# Sheet1.net
KiCad netlist of a schematic drawn in Altium Designer
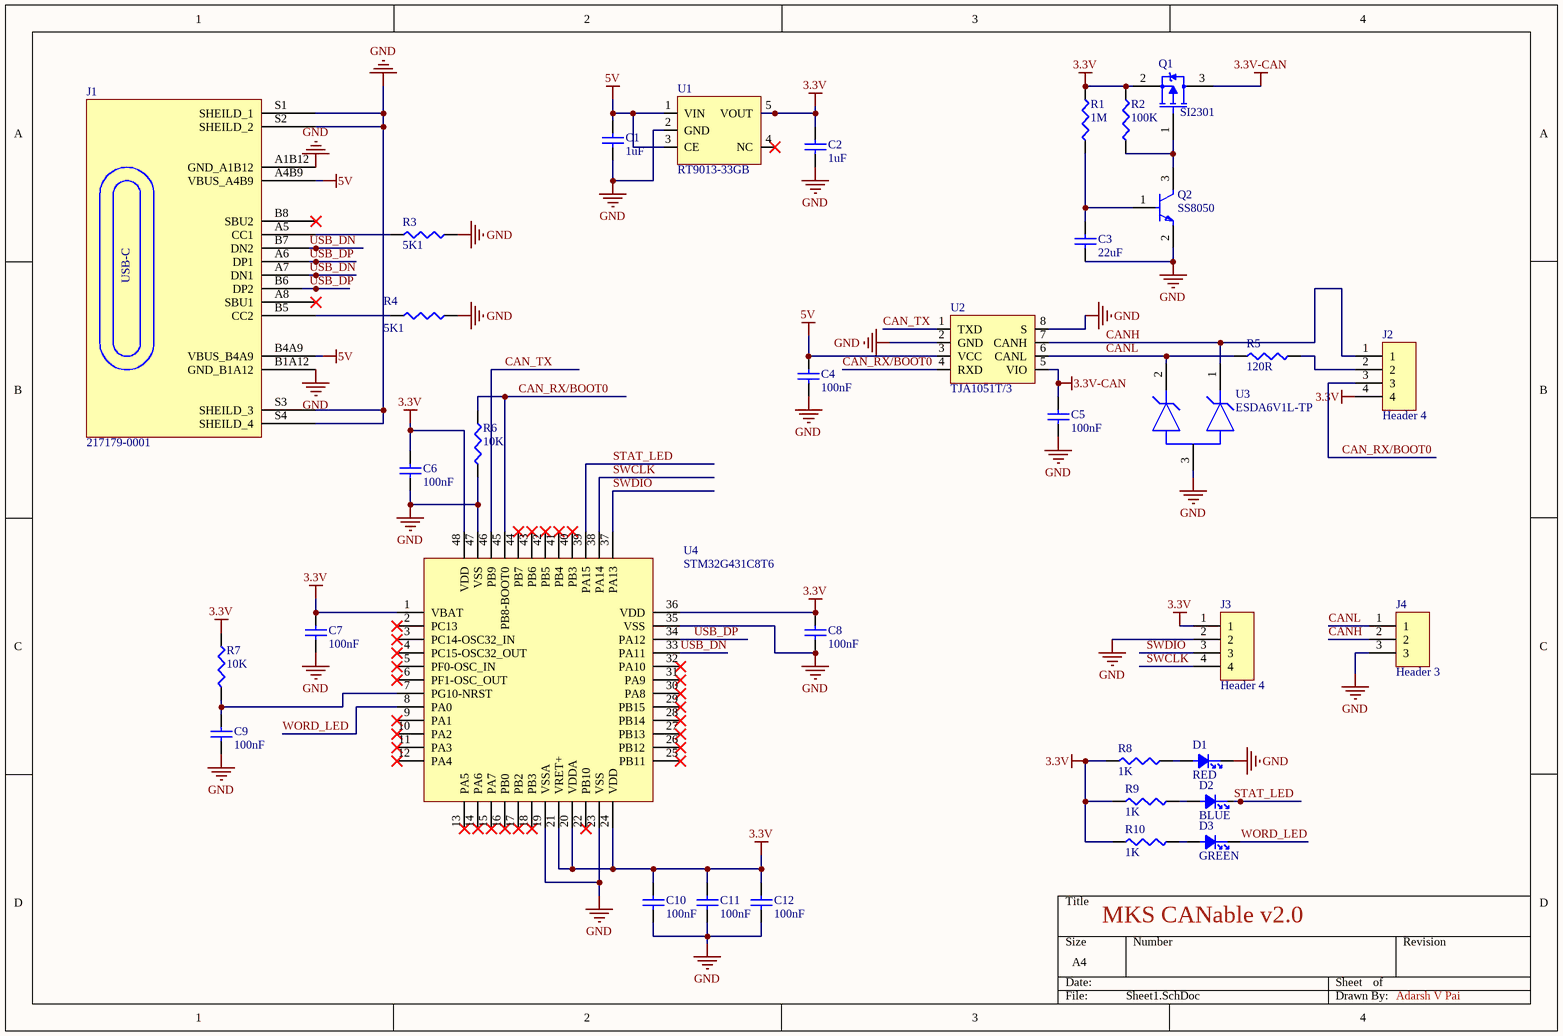
[diagram p0: Sheet1.SchDoc]

(export (version "E")
  (design (tool "Eeschema 10.0.6"))
  (components
    (comp (ref "C1")
      (value "1uF")
      (footprint "CAPC1005X55N")
      (fields
        (field (name "MANUFACTURER") "KEMET")
        (field (name "MANUFACTURER PART NUMBER") "C1206C105K5RACTU")
      )
      (libsource (lib "Schlib1") (part "1uF"))
    )
    (comp (ref "C2")
      (value "1uF")
      (footprint "CAPC1005X55N")
      (fields
        (field (name "MANUFACTURER") "KEMET")
        (field (name "MANUFACTURER PART NUMBER") "C1206C105K5RACTU")
      )
      (libsource (lib "Schlib1") (part "1uF"))
    )
    (comp (ref "C3")
      (value "22uF")
      (footprint "CAPC1005X55N")
      (fields
        (field (name "MANUFACTURER") "Murata")
        (field (name "MANUFACTURER PART NUMBER") "GRM21BR60J226ME39L")
      )
      (libsource (lib "Schlib1") (part "22uF"))
    )
    (comp (ref "C4")
      (value "100nF")
      (footprint "CAPC1005X55N")
      (fields
        (field (name "MANUFACTURER") "KEMET")
        (field (name "MANUFACTURER PART NUMBER") "C0402C104K8PACTU")
      )
      (libsource (lib "Schlib1") (part "100nF"))
    )
    (comp (ref "C5")
      (value "100nF")
      (footprint "CAPC1005X55N")
      (fields
        (field (name "MANUFACTURER") "KEMET")
        (field (name "MANUFACTURER PART NUMBER") "C0402C104K8PACTU")
      )
      (libsource (lib "Schlib1") (part "100nF"))
    )
    (comp (ref "C6")
      (value "100nF")
      (footprint "CAPC1005X55N")
      (fields
        (field (name "MANUFACTURER") "KEMET")
        (field (name "MANUFACTURER PART NUMBER") "C0402C104K8PACTU")
      )
      (libsource (lib "Schlib1") (part "100nF"))
    )
    (comp (ref "C7")
      (value "100nF")
      (footprint "CAPC1005X55N")
      (fields
        (field (name "MANUFACTURER") "KEMET")
        (field (name "MANUFACTURER PART NUMBER") "C0402C104K8PACTU")
      )
      (libsource (lib "Schlib1") (part "100nF"))
    )
    (comp (ref "C8")
      (value "100nF")
      (footprint "CAPC1005X55N")
      (fields
        (field (name "MANUFACTURER") "KEMET")
        (field (name "MANUFACTURER PART NUMBER") "C0402C104K8PACTU")
      )
      (libsource (lib "Schlib1") (part "100nF"))
    )
    (comp (ref "C9")
      (value "100nF")
      (footprint "CAPC1005X55N")
      (fields
        (field (name "MANUFACTURER") "KEMET")
        (field (name "MANUFACTURER PART NUMBER") "C0402C104K8PACTU")
      )
      (libsource (lib "Schlib1") (part "100nF"))
    )
    (comp (ref "C10")
      (value "100nF")
      (footprint "CAPC1005X55N")
      (fields
        (field (name "MANUFACTURER") "KEMET")
        (field (name "MANUFACTURER PART NUMBER") "C0402C104K8PACTU")
      )
      (libsource (lib "Schlib1") (part "100nF"))
    )
    (comp (ref "C11")
      (value "100nF")
      (footprint "CAPC1005X55N")
      (fields
        (field (name "MANUFACTURER") "KEMET")
        (field (name "MANUFACTURER PART NUMBER") "C0402C104K8PACTU")
      )
      (libsource (lib "Schlib1") (part "100nF"))
    )
    (comp (ref "C12")
      (value "100nF")
      (footprint "CAPC1005X55N")
      (fields
        (field (name "MANUFACTURER") "KEMET")
        (field (name "MANUFACTURER PART NUMBER") "C0402C104K8PACTU")
      )
      (libsource (lib "Schlib1") (part "100nF"))
    )
    (comp (ref "D1")
      (value "RED")
      (footprint "LED0402R")
      (description "LED RED 0402 SMD")
      (fields
        (field (name "MANUFACTURER") "Vishay")
        (field (name "MANUFACTURER PART NUMBER") "VLMS1500-GS08")
      )
      (libsource (lib "Schlib1") (part "VLMS1500-GS08"))
    )
    (comp (ref "D2")
      (value "BLUE")
      (footprint "LED0402B")
      (description "Single Color LED, Blue, 0.5mm")
      (fields
        (field (name "MANUFACTURER") "Vishay")
        (field (name "MANUFACTURER PART NUMBER") "VLMB1500-GS08")
      )
      (libsource (lib "Schlib1") (part "VLMB1500-GS08"))
    )
    (comp (ref "D3")
      (value "GREEN")
      (footprint "LED0402G")
      (description "LED YLW-GRN 0402 SMD")
      (fields
        (field (name "MANUFACTURER") "Vishay")
        (field (name "MANUFACTURER PART NUMBER") "VLMG1500-GS08")
      )
      (libsource (lib "Schlib1") (part "VLMG1500-GS08"))
    )
    (comp (ref "J1")
      (value "217179-0001")
      (footprint "FP-2171790001-MFG")
      (description "CONN RCP USB2.0 TYP C 24P SMD RA")
      (fields (field (name "MANUFACTURER") "Molex") (field (name "LCSC PART NUMBER") "C3197684"))
      (libsource (lib "Schlib1") (part "217179-0001"))
    )
    (comp (ref "J2")
      (value "Header 4")
      (footprint "HDR_1X4_1.27MM")
      (fields
        (field (name "MANUFACTURER") "Samtec")
        (field (name "MANUFACTURER PART NUMBER") "FTS-104-01-F-S")
      )
      (libsource (lib "Schlib1") (part "FTS-104-01-F-S"))
    )
    (comp (ref "J3")
      (value "Header 4")
      (footprint "HDR_1X4_1.27MM")
      (fields
        (field (name "MANUFACTURER") "Samtec")
        (field (name "MANUFACTURER PART NUMBER") "FTS-104-01-F-S")
      )
      (libsource (lib "Schlib1") (part "FTS-104-01-F-S"))
    )
    (comp (ref "J4")
      (value "Header 3")
      (footprint "HDR_1X3_1.27MM")
      (fields
        (field (name "MANUFACTURER") "Samtec")
        (field (name "MANUFACTURER PART NUMBER") "FTS-103-01-F-S")
      )
      (libsource (lib "Schlib1") (part "FTS-103-01-F-S"))
    )
    (comp (ref "Q1")
      (value "SI2301")
      (footprint "FP-S-03946-IPC_C")
      (fields
        (field (name "MANUFACTURER") "Vishay Siliconix")
        (field (name "MANUFACTURER PART NUMBER") "SI2301BDS-T1-GE3")
      )
      (libsource (lib "Schlib1") (part "SI2301BDS-T1-GE3"))
    )
    (comp (ref "Q2")
      (value "SS8050")
      (footprint "FP-SS8050-G-IPC_B")
      (description "Small Signal Bipolar Transistor, 1.5A I(C), 25V V(BR)CEO, 1-Element, NPN, Silicon, TO-92")
      (fields
        (field (name "MANUFACTURER") "ON Semiconductor / Fairchild")
        (field (name "MANUFACTURER PART NUMBER") "SS8050DBU")
      )
      (libsource (lib "Schlib1") (part "SS8050"))
    )
    (comp (ref "R1")
      (value "1M")
      (footprint "RESC1005X37N")
      (fields
        (field (name "MANUFACTURER") "Panasonic")
        (field (name "MANUFACTURER PART NUMBER") "ERJ-3EKF1004V")
        (field (name "TOLERANCE") "1%")
      )
      (libsource (lib "Schlib1") (part "1M"))
    )
    (comp (ref "R2")
      (value "100K")
      (footprint "RESC1005X37N")
      (description "NTC Thermistor, 100000ohm, Surface Mount")
      (fields
        (field (name "MANUFACTURER") "Vishay BCcomponents")
        (field (name "MANUFACTURER PART NUMBER") "NTCS0603E3104GXT")
      )
      (libsource (lib "Schlib1") (part "100K"))
    )
    (comp (ref "R3")
      (value "5K1")
      (footprint "RESC1005X37N")
      (description "RES SMD 5.1K OHM 1% 1/16W 0402")
      (fields
        (field (name "MANUFACTURER") "Yageo")
        (field (name "MANUFACTURER PART NUMBER") "AC0402FR-075K1L")
      )
      (libsource (lib "Schlib1") (part "5K1"))
    )
    (comp (ref "R4")
      (value "5K1")
      (footprint "RESC1005X37N")
      (description "RES SMD 5.1K OHM 1% 1/16W 0402")
      (fields
        (field (name "MANUFACTURER") "Yageo")
        (field (name "MANUFACTURER PART NUMBER") "AC0402FR-075K1L")
      )
      (libsource (lib "*") (part "AC0402FR-075K1L"))
    )
    (comp (ref "R5")
      (value "120R")
      (footprint "RESC1005X37N")
      (fields
        (field (name "MANUFACTURER") "Vishay")
        (field (name "MANUFACTURER PART NUMBER") "CRCW0402120RFKED")
        (field (name "TOLERANCE") "1%")
      )
      (libsource (lib "Schlib1") (part "120R"))
    )
    (comp (ref "R6")
      (value "10K")
      (footprint "RESC1005X37N")
      (description "RES SMD 10K OHM 1% 1/16W 0402")
      (fields
        (field (name "MANUFACTURER") "Yageo")
        (field (name "MANUFACTURER PART NUMBER") "AC0402FR-0710KL")
      )
      (libsource (lib "Schlib1") (part "AC0402FR-0710KL"))
    )
    (comp (ref "R7")
      (value "10K")
      (footprint "RESC1005X37N")
      (description "RES SMD 10K OHM 1% 1/16W 0402")
      (fields
        (field (name "MANUFACTURER") "Yageo")
        (field (name "MANUFACTURER PART NUMBER") "AC0402FR-0710KL")
      )
      (libsource (lib "Schlib1") (part "AC0402FR-0710KL"))
    )
    (comp (ref "R8")
      (value "1K")
      (footprint "RESC1005X37N")
      (description "RES 1K OHM 1% 1/16W 0402")
      (fields
        (field (name "MANUFACTURER") "Yageo")
        (field (name "MANUFACTURER PART NUMBER") "RC0402FR-071KL")
      )
      (libsource (lib "Schlib1") (part "1K"))
    )
    (comp (ref "R9")
      (value "1K")
      (footprint "RESC1005X37N")
      (description "RES 1K OHM 1% 1/16W 0402")
      (fields
        (field (name "MANUFACTURER") "Yageo")
        (field (name "MANUFACTURER PART NUMBER") "RC0402FR-071KL")
      )
      (libsource (lib "Schlib1") (part "1K"))
    )
    (comp (ref "R10")
      (value "1K")
      (footprint "RESC1005X37N")
      (description "RES 1K OHM 1% 1/16W 0402")
      (fields
        (field (name "MANUFACTURER") "Yageo")
        (field (name "MANUFACTURER PART NUMBER") "RC0402FR-071KL")
      )
      (libsource (lib "Schlib1") (part "1K"))
    )
    (comp (ref "U1")
      (value "RT9013-33GB")
      (footprint "RT9013-33GB")
      (description "Regulator")
      (fields (field (name "MANUFACTURER") "Richtek"))
      (libsource (lib "Schlib1") (part "RT9013-33GB"))
    )
    (comp (ref "U2")
      (value "TJA1051T/3")
      (footprint "NXP-SOIC-8_M")
      (description "Interface Circuit, 1-Trnsvr, PDSO8")
      (fields
        (field (name "MANUFACTURER") "NXP Semiconductors")
        (field (name "MANUFACTURER PART NUMBER") "TJA1051T/3,118")
      )
      (libsource (lib "Schlib1") (part "TJA1051T/3"))
    )
    (comp (ref "U3")
      (value "ESDA6V1L-TP")
      (footprint "FP-SOT-23-IPC_B")
      (description "Trans Voltage Suppressor Diode, 300W, Unidirectional, 2 Element, Silicon")
      (fields (field (name "MANUFACTURER") "MCC"))
      (libsource (lib "Schlib1") (part "ESDA6V1L-TP"))
    )
    (comp (ref "U4")
      (value "STM32G431C8T6")
      (footprint "STM32")
      (description "Microcontroller")
      (fields (field (name "MANUFACTURER") "STMicroelectronics"))
      (libsource (lib "Schlib1") (part "STM32G431C8T6"))
    )
  )
  (nets
    (net (code "1") (name "/CANH") (class "Default")
      (node (ref "J2") (pin "1") (pinfunction "1_1") (pintype "passive"))
      (node (ref "J4") (pin "2") (pinfunction "2_2") (pintype "passive"))
      (node (ref "U2") (pin "7") (pinfunction "CANH_7") (pintype "passive"))
      (node (ref "U3") (pin "1") (pinfunction "1_1") (pintype "passive"))
    )
    (net (code "2") (name "/CANL") (class "Default")
      (node (ref "J4") (pin "1") (pinfunction "1_1") (pintype "passive"))
      (node (ref "R5") (pin "1") (pinfunction "1_1") (pintype "passive"))
      (node (ref "U2") (pin "6") (pinfunction "CANL_6") (pintype "passive"))
      (node (ref "U3") (pin "2") (pinfunction "2_2") (pintype "passive"))
    )
    (net (code "3") (name "/CAN_RX{slash}BOOT0") (class "Default")
      (node (ref "J2") (pin "3") (pinfunction "3_3") (pintype "passive"))
      (node (ref "R6") (pin "1") (pinfunction "1_1") (pintype "passive"))
      (node (ref "U2") (pin "4") (pinfunction "RXD_4") (pintype "passive"))
      (node (ref "U4") (pin "45") (pinfunction "PB8-BOOT0_45") (pintype "passive"))
    )
    (net (code "4") (name "/CAN_TX") (class "Default")
      (node (ref "U2") (pin "1") (pinfunction "TXD_1") (pintype "passive"))
      (node (ref "U4") (pin "46") (pinfunction "PB9_46") (pintype "passive"))
    )
    (net (code "5") (name "/STAT_LED") (class "Default")
      (node (ref "D2") (pin "1") (pinfunction "1_1") (pintype "passive"))
      (node (ref "U4") (pin "39") (pinfunction "PA15_39") (pintype "passive"))
    )
    (net (code "6") (name "/SWCLK") (class "Default")
      (node (ref "J3") (pin "4") (pinfunction "4_4") (pintype "passive"))
      (node (ref "U4") (pin "38") (pinfunction "PA14_38") (pintype "passive"))
    )
    (net (code "7") (name "/SWDIO") (class "Default")
      (node (ref "J3") (pin "3") (pinfunction "3_3") (pintype "passive"))
      (node (ref "U4") (pin "37") (pinfunction "PA13_37") (pintype "passive"))
    )
    (net (code "8") (name "/USB_DN") (class "Default")
      (node (ref "J1") (pin "A7") (pinfunction "DN1_A7") (pintype "passive"))
      (node (ref "J1") (pin "B7") (pinfunction "DN2_B7") (pintype "passive"))
      (node (ref "U4") (pin "33") (pinfunction "PA11_33") (pintype "passive"))
    )
    (net (code "9") (name "/USB_DP") (class "Default")
      (node (ref "J1") (pin "A6") (pinfunction "DP1_A6") (pintype "passive"))
      (node (ref "J1") (pin "B6") (pinfunction "DP2_B6") (pintype "passive"))
      (node (ref "U4") (pin "34") (pinfunction "PA12_34") (pintype "passive"))
    )
    (net (code "10") (name "/WORD_LED") (class "Default")
      (node (ref "D3") (pin "1") (pinfunction "1_1") (pintype "passive"))
      (node (ref "U4") (pin "8") (pinfunction "PA0_8") (pintype "passive"))
    )
    (net (code "11") (name "3.3V") (class "Default")
      (node (ref "C10") (pin "2") (pinfunction "2_2") (pintype "passive"))
      (node (ref "C11") (pin "2") (pinfunction "2_2") (pintype "passive"))
      (node (ref "C12") (pin "2") (pinfunction "2_2") (pintype "passive"))
      (node (ref "C2") (pin "2") (pinfunction "2_2") (pintype "passive"))
      (node (ref "C6") (pin "2") (pinfunction "2_2") (pintype "passive"))
      (node (ref "C7") (pin "2") (pinfunction "2_2") (pintype "passive"))
      (node (ref "C8") (pin "2") (pinfunction "2_2") (pintype "passive"))
      (node (ref "J2") (pin "4") (pinfunction "4_4") (pintype "passive"))
      (node (ref "J3") (pin "1") (pinfunction "1_1") (pintype "passive"))
      (node (ref "Q1") (pin "2") (pinfunction "S_2") (pintype "passive"))
      (node (ref "R1") (pin "2") (pinfunction "2_2") (pintype "passive"))
      (node (ref "R10") (pin "1") (pinfunction "1_1") (pintype "passive"))
      (node (ref "R2") (pin "2") (pinfunction "2_2") (pintype "passive"))
      (node (ref "R7") (pin "2") (pinfunction "2_2") (pintype "passive"))
      (node (ref "R8") (pin "1") (pinfunction "1_1") (pintype "passive"))
      (node (ref "R9") (pin "1") (pinfunction "1_1") (pintype "passive"))
      (node (ref "U1") (pin "5") (pinfunction "VOUT_5") (pintype "passive"))
      (node (ref "U4") (pin "1") (pinfunction "VBAT_1") (pintype "passive"))
      (node (ref "U4") (pin "20") (pinfunction "VDDA_20") (pintype "passive"))
      (node (ref "U4") (pin "21") (pinfunction "VRET+_21") (pintype "passive"))
      (node (ref "U4") (pin "24") (pinfunction "VDD_24") (pintype "passive"))
      (node (ref "U4") (pin "36") (pinfunction "VDD_36") (pintype "passive"))
      (node (ref "U4") (pin "48") (pinfunction "VDD_48") (pintype "passive"))
    )
    (net (code "12") (name "3.3V-CAN") (class "Default")
      (node (ref "C5") (pin "2") (pinfunction "2_2") (pintype "passive"))
      (node (ref "Q1") (pin "3") (pinfunction "D_3") (pintype "passive"))
      (node (ref "U2") (pin "5") (pinfunction "VIO_5") (pintype "passive"))
    )
    (net (code "13") (name "5V") (class "Default")
      (node (ref "C1") (pin "2") (pinfunction "2_2") (pintype "passive"))
      (node (ref "C4") (pin "2") (pinfunction "2_2") (pintype "passive"))
      (node (ref "J1") (pin "A4B9") (pinfunction "VBUS_A4B9_A4B9") (pintype "passive"))
      (node (ref "J1") (pin "B4A9") (pinfunction "VBUS_B4A9_B4A9") (pintype "passive"))
      (node (ref "U1") (pin "1") (pinfunction "VIN_1") (pintype "passive"))
      (node (ref "U1") (pin "3") (pinfunction "CE_3") (pintype "passive"))
      (node (ref "U2") (pin "3") (pinfunction "VCC_3") (pintype "passive"))
    )
    (net (code "14") (name "GND") (class "Default")
      (node (ref "C1") (pin "1") (pinfunction "1_1") (pintype "passive"))
      (node (ref "C10") (pin "1") (pinfunction "1_1") (pintype "passive"))
      (node (ref "C11") (pin "1") (pinfunction "1_1") (pintype "passive"))
      (node (ref "C12") (pin "1") (pinfunction "1_1") (pintype "passive"))
      (node (ref "C2") (pin "1") (pinfunction "1_1") (pintype "passive"))
      (node (ref "C3") (pin "1") (pinfunction "1_1") (pintype "passive"))
      (node (ref "C4") (pin "1") (pinfunction "1_1") (pintype "passive"))
      (node (ref "C5") (pin "1") (pinfunction "1_1") (pintype "passive"))
      (node (ref "C6") (pin "1") (pinfunction "1_1") (pintype "passive"))
      (node (ref "C7") (pin "1") (pinfunction "1_1") (pintype "passive"))
      (node (ref "C8") (pin "1") (pinfunction "1_1") (pintype "passive"))
      (node (ref "C9") (pin "1") (pinfunction "1_1") (pintype "passive"))
      (node (ref "D1") (pin "1") (pinfunction "1_1") (pintype "passive"))
      (node (ref "J1") (pin "A1B12") (pinfunction "GND_A1B12_A1B12") (pintype "passive"))
      (node (ref "J1") (pin "B1A12") (pinfunction "GND_B1A12_B1A12") (pintype "passive"))
      (node (ref "J1") (pin "S1") (pinfunction "SHEILD_1_S1") (pintype "passive"))
      (node (ref "J1") (pin "S2") (pinfunction "SHEILD_2_S2") (pintype "passive"))
      (node (ref "J1") (pin "S3") (pinfunction "SHEILD_3_S3") (pintype "passive"))
      (node (ref "J1") (pin "S4") (pinfunction "SHEILD_4_S4") (pintype "passive"))
      (node (ref "J3") (pin "2") (pinfunction "2_2") (pintype "passive"))
      (node (ref "J4") (pin "3") (pinfunction "3_3") (pintype "passive"))
      (node (ref "Q2") (pin "2") (pinfunction "E_2") (pintype "passive"))
      (node (ref "R3") (pin "2") (pinfunction "2_2") (pintype "passive"))
      (node (ref "R4") (pin "2") (pinfunction "2_2") (pintype "passive"))
      (node (ref "R6") (pin "2") (pinfunction "2_2") (pintype "passive"))
      (node (ref "U1") (pin "2") (pinfunction "GND_2") (pintype "passive"))
      (node (ref "U2") (pin "2") (pinfunction "GND_2") (pintype "passive"))
      (node (ref "U2") (pin "8") (pinfunction "S_8") (pintype "passive"))
      (node (ref "U3") (pin "3") (pinfunction "3_3") (pintype "passive"))
      (node (ref "U4") (pin "19") (pinfunction "VSSA_19") (pintype "passive"))
      (node (ref "U4") (pin "23") (pinfunction "VSS_23") (pintype "passive"))
      (node (ref "U4") (pin "35") (pinfunction "VSS_35") (pintype "passive"))
      (node (ref "U4") (pin "47") (pinfunction "VSS_47") (pintype "passive"))
    )
    (net (code "15") (name "Net-(D1-Pad2)") (class "Default")
      (node (ref "D1") (pin "2") (pinfunction "2_2") (pintype "passive"))
      (node (ref "R8") (pin "2") (pinfunction "2_2") (pintype "passive"))
    )
    (net (code "16") (name "Net-(D2-Pad2)") (class "Default")
      (node (ref "D2") (pin "2") (pinfunction "2_2") (pintype "passive"))
      (node (ref "R9") (pin "2") (pinfunction "2_2") (pintype "passive"))
    )
    (net (code "17") (name "Net-(D3-Pad2)") (class "Default")
      (node (ref "D3") (pin "2") (pinfunction "2_2") (pintype "passive"))
      (node (ref "R10") (pin "2") (pinfunction "2_2") (pintype "passive"))
    )
    (net (code "18") (name "Net-(J1-CC1)") (class "Default")
      (node (ref "J1") (pin "A5") (pinfunction "CC1_A5") (pintype "passive"))
      (node (ref "R3") (pin "1") (pinfunction "1_1") (pintype "passive"))
    )
    (net (code "19") (name "Net-(J1-CC2)") (class "Default")
      (node (ref "J1") (pin "B5") (pinfunction "CC2_B5") (pintype "passive"))
      (node (ref "R4") (pin "1") (pinfunction "1_1") (pintype "passive"))
    )
    (net (code "20") (name "Net-(J2-Pad2)") (class "Default")
      (node (ref "J2") (pin "2") (pinfunction "2_2") (pintype "passive"))
      (node (ref "R5") (pin "2") (pinfunction "2_2") (pintype "passive"))
    )
    (net (code "21") (name "Net-(Q1-G)") (class "Default")
      (node (ref "Q1") (pin "1") (pinfunction "G_1") (pintype "passive"))
      (node (ref "Q2") (pin "3") (pinfunction "C_3") (pintype "passive"))
      (node (ref "R2") (pin "1") (pinfunction "1_1") (pintype "passive"))
    )
    (net (code "22") (name "Net-(Q2-B)") (class "Default")
      (node (ref "C3") (pin "2") (pinfunction "2_2") (pintype "passive"))
      (node (ref "Q2") (pin "1") (pinfunction "B_1") (pintype "passive"))
      (node (ref "R1") (pin "1") (pinfunction "1_1") (pintype "passive"))
    )
    (net (code "23") (name "Net-(U4-PG10-NRST)") (class "Default")
      (node (ref "C9") (pin "2") (pinfunction "2_2") (pintype "passive"))
      (node (ref "R7") (pin "1") (pinfunction "1_1") (pintype "passive"))
      (node (ref "U4") (pin "7") (pinfunction "PG10-NRST_7") (pintype "passive"))
    )
    (net (code "24") (name "unconnected-(J1-SBU1-PadA8)") (class "Default")
      (node (ref "J1") (pin "A8") (pinfunction "SBU1_A8") (pintype "passive+no_connect"))
    )
    (net (code "25") (name "unconnected-(J1-SBU2-PadB8)") (class "Default")
      (node (ref "J1") (pin "B8") (pinfunction "SBU2_B8") (pintype "passive+no_connect"))
    )
    (net (code "26") (name "unconnected-(U1-NC-Pad4)") (class "Default")
      (node (ref "U1") (pin "4") (pinfunction "NC_4") (pintype "passive+no_connect"))
    )
    (net (code "27") (name "unconnected-(U4-PA1-Pad9)") (class "Default")
      (node (ref "U4") (pin "9") (pinfunction "PA1_9") (pintype "passive+no_connect"))
    )
    (net (code "28") (name "unconnected-(U4-PA2-Pad10)") (class "Default")
      (node (ref "U4") (pin "10") (pinfunction "PA2_10") (pintype "passive+no_connect"))
    )
    (net (code "29") (name "unconnected-(U4-PA3-Pad11)") (class "Default")
      (node (ref "U4") (pin "11") (pinfunction "PA3_11") (pintype "passive+no_connect"))
    )
    (net (code "30") (name "unconnected-(U4-PA4-Pad12)") (class "Default")
      (node (ref "U4") (pin "12") (pinfunction "PA4_12") (pintype "passive+no_connect"))
    )
    (net (code "31") (name "unconnected-(U4-PA5-Pad13)") (class "Default")
      (node (ref "U4") (pin "13") (pinfunction "PA5_13") (pintype "passive+no_connect"))
    )
    (net (code "32") (name "unconnected-(U4-PA6-Pad14)") (class "Default")
      (node (ref "U4") (pin "14") (pinfunction "PA6_14") (pintype "passive+no_connect"))
    )
    (net (code "33") (name "unconnected-(U4-PA7-Pad15)") (class "Default")
      (node (ref "U4") (pin "15") (pinfunction "PA7_15") (pintype "passive+no_connect"))
    )
    (net (code "34") (name "unconnected-(U4-PA8-Pad30)") (class "Default")
      (node (ref "U4") (pin "30") (pinfunction "PA8_30") (pintype "passive+no_connect"))
    )
    (net (code "35") (name "unconnected-(U4-PA9-Pad31)") (class "Default")
      (node (ref "U4") (pin "31") (pinfunction "PA9_31") (pintype "passive+no_connect"))
    )
    (net (code "36") (name "unconnected-(U4-PA10-Pad32)") (class "Default")
      (node (ref "U4") (pin "32") (pinfunction "PA10_32") (pintype "passive+no_connect"))
    )
    (net (code "37") (name "unconnected-(U4-PB0-Pad16)") (class "Default")
      (node (ref "U4") (pin "16") (pinfunction "PB0_16") (pintype "passive+no_connect"))
    )
    (net (code "38") (name "unconnected-(U4-PB2-Pad17)") (class "Default")
      (node (ref "U4") (pin "17") (pinfunction "PB2_17") (pintype "passive+no_connect"))
    )
    (net (code "39") (name "unconnected-(U4-PB3-Pad18)") (class "Default")
      (node (ref "U4") (pin "18") (pinfunction "PB3_18") (pintype "passive+no_connect"))
    )
    (net (code "40") (name "unconnected-(U4-PB3-Pad40)") (class "Default")
      (node (ref "U4") (pin "40") (pinfunction "PB3_40") (pintype "passive+no_connect"))
    )
    (net (code "41") (name "unconnected-(U4-PB4-Pad41)") (class "Default")
      (node (ref "U4") (pin "41") (pinfunction "PB4_41") (pintype "passive+no_connect"))
    )
    (net (code "42") (name "unconnected-(U4-PB5-Pad42)") (class "Default")
      (node (ref "U4") (pin "42") (pinfunction "PB5_42") (pintype "passive+no_connect"))
    )
    (net (code "43") (name "unconnected-(U4-PB6-Pad43)") (class "Default")
      (node (ref "U4") (pin "43") (pinfunction "PB6_43") (pintype "passive+no_connect"))
    )
    (net (code "44") (name "unconnected-(U4-PB7-Pad44)") (class "Default")
      (node (ref "U4") (pin "44") (pinfunction "PB7_44") (pintype "passive+no_connect"))
    )
    (net (code "45") (name "unconnected-(U4-PB10-Pad22)") (class "Default")
      (node (ref "U4") (pin "22") (pinfunction "PB10_22") (pintype "passive+no_connect"))
    )
    (net (code "46") (name "unconnected-(U4-PB11-Pad25)") (class "Default")
      (node (ref "U4") (pin "25") (pinfunction "PB11_25") (pintype "passive+no_connect"))
    )
    (net (code "47") (name "unconnected-(U4-PB12-Pad26)") (class "Default")
      (node (ref "U4") (pin "26") (pinfunction "PB12_26") (pintype "passive+no_connect"))
    )
    (net (code "48") (name "unconnected-(U4-PB13-Pad27)") (class "Default")
      (node (ref "U4") (pin "27") (pinfunction "PB13_27") (pintype "passive+no_connect"))
    )
    (net (code "49") (name "unconnected-(U4-PB14-Pad28)") (class "Default")
      (node (ref "U4") (pin "28") (pinfunction "PB14_28") (pintype "passive+no_connect"))
    )
    (net (code "50") (name "unconnected-(U4-PB15-Pad29)") (class "Default")
      (node (ref "U4") (pin "29") (pinfunction "PB15_29") (pintype "passive+no_connect"))
    )
    (net (code "51") (name "unconnected-(U4-PC13-Pad2)") (class "Default")
      (node (ref "U4") (pin "2") (pinfunction "PC13_2") (pintype "passive+no_connect"))
    )
    (net (code "52") (name "unconnected-(U4-PC14-OSC32_IN-Pad3)") (class "Default")
      (node (ref "U4") (pin "3") (pinfunction "PC14-OSC32_IN_3") (pintype "passive+no_connect"))
    )
    (net (code "53") (name "unconnected-(U4-PC15-OSC32_OUT-Pad4)") (class "Default")
      (node (ref "U4") (pin "4") (pinfunction "PC15-OSC32_OUT_4") (pintype "passive+no_connect"))
    )
    (net (code "54") (name "unconnected-(U4-PF0-OSC_IN-Pad5)") (class "Default")
      (node (ref "U4") (pin "5") (pinfunction "PF0-OSC_IN_5") (pintype "passive+no_connect"))
    )
    (net (code "55") (name "unconnected-(U4-PF1-OSC_OUT-Pad6)") (class "Default")
      (node (ref "U4") (pin "6") (pinfunction "PF1-OSC_OUT_6") (pintype "passive+no_connect"))
    )
  )
)
